# USB.net
KiCad netlist of a schematic drawn in Altium Designer
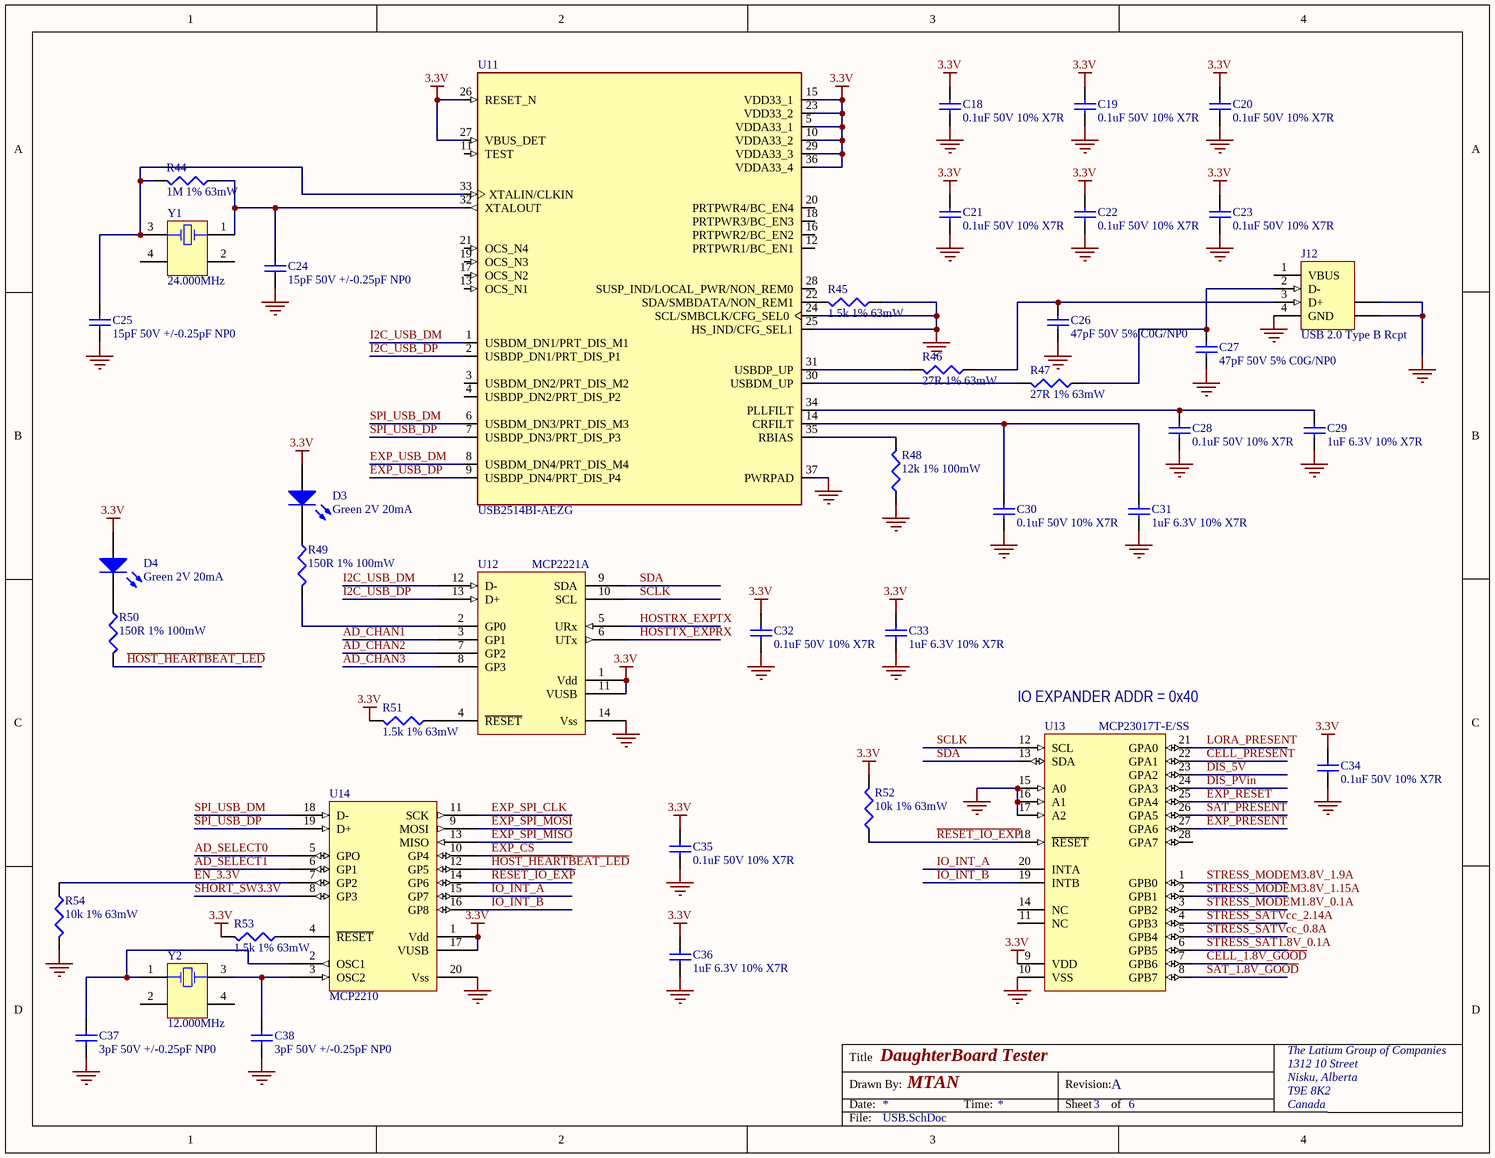
[diagram p0: USB.SchDoc]

(export (version "E")
  (design (tool "Eeschema 10.0.6"))
  (components
    (comp (ref "C18")
      (value "0.1uF 50V 10% X7R")
      (footprint "CAPC1005L")
      (description "Capacitor")
      (libsource (lib "Miscellaneous Devices") (part "Cap"))
    )
    (comp (ref "C19")
      (value "0.1uF 50V 10% X7R")
      (footprint "CAPC1005L")
      (description "Capacitor")
      (libsource (lib "Miscellaneous Devices") (part "Cap"))
    )
    (comp (ref "C20")
      (value "0.1uF 50V 10% X7R")
      (footprint "CAPC1005L")
      (description "Capacitor")
      (libsource (lib "Miscellaneous Devices") (part "Cap"))
    )
    (comp (ref "C21")
      (value "0.1uF 50V 10% X7R")
      (footprint "CAPC1005L")
      (description "Capacitor")
      (libsource (lib "Miscellaneous Devices") (part "Cap"))
    )
    (comp (ref "C22")
      (value "0.1uF 50V 10% X7R")
      (footprint "CAPC1005L")
      (description "Capacitor")
      (libsource (lib "Miscellaneous Devices") (part "Cap"))
    )
    (comp (ref "C23")
      (value "0.1uF 50V 10% X7R")
      (footprint "CAPC1005L")
      (description "Capacitor")
      (libsource (lib "Miscellaneous Devices") (part "Cap"))
    )
    (comp (ref "C24")
      (value "15pF 50V +/-0.25pF NP0")
      (footprint "CAPC1005L")
      (description "Capacitor")
      (libsource (lib "Miscellaneous Devices") (part "Cap"))
    )
    (comp (ref "C25")
      (value "15pF 50V +/-0.25pF NP0")
      (footprint "CAPC1005L")
      (description "Capacitor")
      (libsource (lib "Miscellaneous Devices") (part "Cap"))
    )
    (comp (ref "C26")
      (value "47pF 50V 5% C0G/NP0")
      (footprint "CAPC1005L")
      (description "Capacitor")
      (libsource (lib "Miscellaneous Devices") (part "Cap"))
    )
    (comp (ref "C27")
      (value "47pF 50V 5% C0G/NP0")
      (footprint "CAPC1005L")
      (description "Capacitor")
      (libsource (lib "Miscellaneous Devices") (part "Cap"))
    )
    (comp (ref "C28")
      (value "0.1uF 50V 10% X7R")
      (footprint "CAPC1005L")
      (description "Capacitor")
      (libsource (lib "Miscellaneous Devices") (part "Cap"))
    )
    (comp (ref "C29")
      (value "1uF 6.3V 10% X7R")
      (footprint "CAPC1005L")
      (description "Capacitor")
      (libsource (lib "Miscellaneous Devices") (part "Cap"))
    )
    (comp (ref "C30")
      (value "0.1uF 50V 10% X7R")
      (footprint "CAPC1005L")
      (description "Capacitor")
      (libsource (lib "Miscellaneous Devices") (part "Cap"))
    )
    (comp (ref "C31")
      (value "1uF 6.3V 10% X7R")
      (footprint "CAPC1005L")
      (description "Capacitor")
      (libsource (lib "Miscellaneous Devices") (part "Cap"))
    )
    (comp (ref "C32")
      (value "0.1uF 50V 10% X7R")
      (footprint "CAPC1005L")
      (description "Capacitor")
      (libsource (lib "Miscellaneous Devices") (part "Cap"))
    )
    (comp (ref "C33")
      (value "1uF 6.3V 10% X7R")
      (footprint "CAPC1005L")
      (description "Capacitor")
      (libsource (lib "Miscellaneous Devices") (part "Cap"))
    )
    (comp (ref "C34")
      (value "0.1uF 50V 10% X7R")
      (footprint "CAPC1005L")
      (description "Capacitor")
      (libsource (lib "Miscellaneous Devices") (part "Cap"))
    )
    (comp (ref "C35")
      (value "0.1uF 50V 10% X7R")
      (footprint "CAPC1005L")
      (description "Capacitor")
      (libsource (lib "Miscellaneous Devices") (part "Cap"))
    )
    (comp (ref "C36")
      (value "1uF 6.3V 10% X7R")
      (footprint "CAPC1005L")
      (description "Capacitor")
      (libsource (lib "Miscellaneous Devices") (part "Cap"))
    )
    (comp (ref "C37")
      (value "3pF 50V +/-0.25pF NP0")
      (footprint "CAPC1005L")
      (description "Capacitor")
      (libsource (lib "Miscellaneous Devices") (part "Cap"))
    )
    (comp (ref "C38")
      (value "3pF 50V +/-0.25pF NP0")
      (footprint "CAPC1005L")
      (description "Capacitor")
      (libsource (lib "Miscellaneous Devices") (part "Cap"))
    )
    (comp (ref "D3")
      (value "Green 2V 20mA")
      (footprint "CD1608-0603")
      (description "LED GREEN CLEAR 0603 SMD")
      (fields
        (field (name "MANUFACTURER") "Wurth Electronics Inc")
        (field (name "MANUFACTURER PART NUMBER") "150060VS75000")
      )
      (libsource (lib "Miscellaneous Devices") (part "LED2"))
    )
    (comp (ref "D4")
      (value "Green 2V 20mA")
      (footprint "CD1608-0603")
      (description "LED GREEN CLEAR 0603 SMD")
      (fields
        (field (name "MANUFACTURER") "Wurth Electronics Inc")
        (field (name "MANUFACTURER PART NUMBER") "150060VS75000")
      )
      (libsource (lib "Miscellaneous Devices") (part "LED2"))
    )
    (comp (ref "J12")
      (value "USB 2.0 Type B Rcpt")
      (footprint "1-1734346-1")
      (description "CONN RCPT USB2.0 TYPEB 4P SMD RA")
      (fields
        (field (name "MANUFACTURER") "TE Connectivity AMP Connectors")
        (field (name "MANUFACTURER PART NUMBER") "1-1734346-1")
      )
      (libsource (lib "AMP Serial Bus USB") (part "1-1470156-1"))
    )
    (comp (ref "R44")
      (value "1M 1% 63mW")
      (footprint "RESC1005L")
      (description "Resistor")
      (libsource (lib "Miscellaneous Devices") (part "Res3"))
    )
    (comp (ref "R45")
      (value "1.5k 1% 63mW")
      (footprint "RESC1005L")
      (description "Resistor")
      (libsource (lib "Miscellaneous Devices") (part "Res3"))
    )
    (comp (ref "R46")
      (value "27R 1% 63mW")
      (footprint "RESC1005L")
      (description "Resistor")
      (libsource (lib "Miscellaneous Devices") (part "Res3"))
    )
    (comp (ref "R47")
      (value "27R 1% 63mW")
      (footprint "RESC1005L")
      (description "Resistor")
      (libsource (lib "Miscellaneous Devices") (part "Res3"))
    )
    (comp (ref "R48")
      (value "12k 1% 100mW")
      (footprint "J1-0603")
      (description "Resistor")
      (libsource (lib "Miscellaneous Devices") (part "Res3"))
    )
    (comp (ref "R49")
      (value "150R 1% 100mW")
      (footprint "RESC1608L")
      (description "Resistor")
      (libsource (lib "Miscellaneous Devices") (part "Res3"))
    )
    (comp (ref "R50")
      (value "150R 1% 100mW")
      (footprint "RESC1608L")
      (description "Resistor")
      (libsource (lib "Miscellaneous Devices") (part "Res3"))
    )
    (comp (ref "R51")
      (value "1.5k 1% 63mW")
      (footprint "RESC1005L")
      (description "Resistor")
      (libsource (lib "Miscellaneous Devices") (part "Res3"))
    )
    (comp (ref "R52")
      (value "10k 1% 63mW")
      (footprint "RESC1005L")
      (description "Resistor")
      (libsource (lib "Miscellaneous Devices") (part "Res3"))
    )
    (comp (ref "R53")
      (value "1.5k 1% 63mW")
      (footprint "RESC1005L")
      (description "Resistor")
      (libsource (lib "Miscellaneous Devices") (part "Res3"))
    )
    (comp (ref "R54")
      (value "10k 1% 63mW")
      (footprint "RESC1005L")
      (description "Resistor")
      (libsource (lib "Miscellaneous Devices") (part "Res3"))
    )
    (comp (ref "U11")
      (value "USB2514BI-AEZG")
      (footprint "QFN50P600X600X100-37N")
      (description "IC CONTROLLER USB 36QFN")
      (fields
        (field (name "MANUFACTURER") "Microchip Technology")
        (field (name "MANUFACTURER PART NUMBER") "USB2514BI-AEZG-TR")
      )
      (libsource (lib "USB2514BI-AEZG") (part "USB2514BI-AEZG"))
    )
    (comp (ref "U12")
      (value "MCP2221A")
      (footprint "TSSOP14_L")
      (description "IC USB TO I2C/UART 14TSSOP")
      (fields
        (field (name "MANUFACTURER") "Microchip Technology")
        (field (name "MANUFACTURER PART NUMBER") "MCP2221AT-I/ST")
      )
      (libsource (lib "Latium Component Library") (part "MCP2221A"))
    )
    (comp (ref "U13")
      (value "MCP23017T-E/SS")
      (footprint "SSOP-SS28_L")
      (description "IC I/O EXPANDER 16BIT I2C 28SSOP")
      (fields (field (name "MANUFACTURER") "Microchip Technology"))
      (libsource (lib "Microchip Interface") (part "MCP23017-E/SS"))
    )
    (comp (ref "U14")
      (value "MCP2210")
      (footprint "SSOP20_L")
      (description "IC CONVERTER USB-SPI 20-SSOP")
      (fields
        (field (name "MANUFACTURER") "Microchip Technology")
        (field (name "MANUFACTURER PART NUMBER") "MCP2210T-I/SS")
      )
      (libsource (lib "Latium Component Library") (part "MCP2210"))
    )
    (comp (ref "Y1")
      (value "24.000MHz")
      (footprint "CFPX-5")
      (description "CRYSTAL 24.0000MHZ 18PF SMD")
      (fields
        (field (name "MANUFACTURER PART NUMBER") "TSX-3225 24.0000MF18X-C0")
        (field (name "MANUFACTURER") "Epson")
      )
      (libsource (lib "C-MAC Crystal Oscillator") (part "CFPX-5"))
    )
    (comp (ref "Y2")
      (value "12.000MHz")
      (footprint "CFPX-5")
      (description "CRYSTAL 12.0000MHZ 8PF SMD")
      (fields
        (field (name "MANUFACTURER PART NUMBER") "NX3225SA-12.000M-STD-CRS-2")
        (field (name "MANUFACTURER") "NDK America Inc")
      )
      (libsource (lib "") (part "CFPX-5_1"))
    )
  )
  (nets
    (net (code "1") (name "/AD_CHAN1") (class "Default")
      (node (ref "U12") (pin "3") (pinfunction "GP1_3") (pintype "passive"))
    )
    (net (code "2") (name "/AD_CHAN2") (class "Default")
      (node (ref "U12") (pin "7") (pinfunction "GP2_7") (pintype "passive"))
    )
    (net (code "3") (name "/AD_CHAN3") (class "Default")
      (node (ref "U12") (pin "8") (pinfunction "GP3_8") (pintype "passive"))
    )
    (net (code "4") (name "/AD_SELECT0") (class "Default")
      (node (ref "U14") (pin "5") (pinfunction "GPO_5") (pintype "bidirectional"))
    )
    (net (code "5") (name "/AD_SELECT1") (class "Default")
      (node (ref "U14") (pin "6") (pinfunction "GP1_6") (pintype "bidirectional"))
    )
    (net (code "6") (name "/CELL_PRESENT") (class "Default")
      (node (ref "U13") (pin "22") (pinfunction "GPA1_22") (pintype "bidirectional"))
    )
    (net (code "7") (name "/DIS_5V") (class "Default")
      (node (ref "U13") (pin "23") (pinfunction "GPA2_23") (pintype "bidirectional"))
    )
    (net (code "8") (name "/DIS_PVin") (class "Default")
      (node (ref "U13") (pin "24") (pinfunction "GPA3_24") (pintype "bidirectional"))
    )
    (net (code "9") (name "/EN_3.3V") (class "Default")
      (node (ref "R54") (pin "1") (pinfunction "1_1") (pintype "passive"))
      (node (ref "U14") (pin "7") (pinfunction "GP2_7") (pintype "bidirectional"))
    )
    (net (code "10") (name "/EXP_PRESENT") (class "Default")
      (node (ref "U13") (pin "27") (pinfunction "GPA6_27") (pintype "bidirectional"))
    )
    (net (code "11") (name "/EXP_RESET") (class "Default")
      (node (ref "U13") (pin "25") (pinfunction "GPA4_25") (pintype "bidirectional"))
    )
    (net (code "12") (name "/EXP_SPI_CLK") (class "Default")
      (node (ref "U14") (pin "11") (pinfunction "SCK_11") (pintype "output"))
    )
    (net (code "13") (name "/EXP_SPI_MISO") (class "Default")
      (node (ref "U14") (pin "13") (pinfunction "MISO_13") (pintype "input"))
    )
    (net (code "14") (name "/EXP_SPI_MOSI") (class "Default")
      (node (ref "U14") (pin "9") (pinfunction "MOSI_9") (pintype "output"))
    )
    (net (code "15") (name "/EXP_USB_DM") (class "Default")
      (node (ref "U11") (pin "8") (pinfunction "USBDM_DN4/PRT_DIS_M4_8") (pintype "bidirectional"))
    )
    (net (code "16") (name "/EXP_USB_DP") (class "Default")
      (node (ref "U11") (pin "9") (pinfunction "USBDP_DN4/PRT_DIS_P4_9") (pintype "bidirectional"))
    )
    (net (code "17") (name "/HOSTRX_EXPTX") (class "Default")
      (node (ref "U12") (pin "5") (pinfunction "URx_5") (pintype "input"))
    )
    (net (code "18") (name "/HOSTTX_EXPRX") (class "Default")
      (node (ref "U12") (pin "6") (pinfunction "UTx_6") (pintype "output"))
    )
    (net (code "19") (name "/I2C_USB_DM") (class "Default")
      (node (ref "U11") (pin "1") (pinfunction "USBDM_DN1/PRT_DIS_M1_1") (pintype "bidirectional"))
      (node (ref "U12") (pin "12") (pinfunction "D-_12") (pintype "input"))
    )
    (net (code "20") (name "/I2C_USB_DP") (class "Default")
      (node (ref "U11") (pin "2") (pinfunction "USBDP_DN1/PRT_DIS_P1_2") (pintype "bidirectional"))
      (node (ref "U12") (pin "13") (pinfunction "D+_13") (pintype "input"))
    )
    (net (code "21") (name "/IO_INT_A") (class "Default")
      (node (ref "U13") (pin "20") (pinfunction "INTA_20") (pintype "open_collector"))
      (node (ref "U14") (pin "15") (pinfunction "GP7_15") (pintype "bidirectional"))
    )
    (net (code "22") (name "/IO_INT_B") (class "Default")
      (node (ref "U13") (pin "19") (pinfunction "INTB_19") (pintype "open_collector"))
      (node (ref "U14") (pin "16") (pinfunction "GP8_16") (pintype "bidirectional"))
    )
    (net (code "23") (name "/LORA_PRESENT") (class "Default")
      (node (ref "U13") (pin "21") (pinfunction "GPA0_21") (pintype "bidirectional"))
    )
    (net (code "24") (name "/SAT_PRESENT") (class "Default")
      (node (ref "U13") (pin "26") (pinfunction "GPA5_26") (pintype "bidirectional"))
    )
    (net (code "25") (name "/SCLK") (class "Default")
      (node (ref "U12") (pin "10") (pinfunction "SCL_10") (pintype "open_collector"))
      (node (ref "U13") (pin "12") (pinfunction "SCL_12") (pintype "input"))
    )
    (net (code "26") (name "/SDA") (class "Default")
      (node (ref "U12") (pin "9") (pinfunction "SDA_9") (pintype "open_collector"))
      (node (ref "U13") (pin "13") (pinfunction "SDA_13") (pintype "bidirectional"))
    )
    (net (code "27") (name "/SPI_USB_DM") (class "Default")
      (node (ref "U11") (pin "6") (pinfunction "USBDM_DN3/PRT_DIS_M3_6") (pintype "bidirectional"))
      (node (ref "U14") (pin "18") (pinfunction "D-_18") (pintype "input"))
    )
    (net (code "28") (name "/SPI_USB_DP") (class "Default")
      (node (ref "U11") (pin "7") (pinfunction "USBDP_DN3/PRT_DIS_P3_7") (pintype "bidirectional"))
      (node (ref "U14") (pin "19") (pinfunction "D+_19") (pintype "input"))
    )
    (net (code "29") (name "/STRESS_MODEM1.8V_0.1A") (class "Default")
      (node (ref "U13") (pin "3") (pinfunction "GPB2_3") (pintype "bidirectional"))
    )
    (net (code "30") (name "/STRESS_MODEM3.8V_1.9A") (class "Default")
      (node (ref "U13") (pin "1") (pinfunction "GPB0_1") (pintype "bidirectional"))
    )
    (net (code "31") (name "/STRESS_MODEM3.8V_1.15A") (class "Default")
      (node (ref "U13") (pin "2") (pinfunction "GPB1_2") (pintype "bidirectional"))
    )
    (net (code "32") (name "/STRESS_SAT1.8V_0.1A") (class "Default")
      (node (ref "U13") (pin "6") (pinfunction "GPB5_6") (pintype "bidirectional"))
    )
    (net (code "33") (name "/STRESS_SATVcc_0.8A") (class "Default")
      (node (ref "U13") (pin "5") (pinfunction "GPB4_5") (pintype "bidirectional"))
    )
    (net (code "34") (name "/STRESS_SATVcc_2.14A") (class "Default")
      (node (ref "U13") (pin "4") (pinfunction "GPB3_4") (pintype "bidirectional"))
    )
    (net (code "35") (name "/~{CELL_1.8V_GOOD}") (class "Default")
      (node (ref "U13") (pin "7") (pinfunction "GPB6_7") (pintype "bidirectional"))
    )
    (net (code "36") (name "/~{EXP_CS}") (class "Default")
      (node (ref "U14") (pin "10") (pinfunction "GP4_10") (pintype "bidirectional"))
    )
    (net (code "37") (name "/~{HOST_HEARTBEAT_LED}") (class "Default")
      (node (ref "R50") (pin "2") (pinfunction "2_2") (pintype "passive"))
      (node (ref "U14") (pin "12") (pinfunction "GP5_12") (pintype "bidirectional"))
    )
    (net (code "38") (name "/~{RESET_IO_EXP}") (class "Default")
      (node (ref "R52") (pin "1") (pinfunction "1_1") (pintype "passive"))
      (node (ref "U13") (pin "18") (pinfunction "~{RESET}_18") (pintype "input"))
      (node (ref "U14") (pin "14") (pinfunction "GP6_14") (pintype "bidirectional"))
    )
    (net (code "39") (name "/~{SAT_1.8V_GOOD}") (class "Default")
      (node (ref "U13") (pin "8") (pinfunction "GPB7_8") (pintype "bidirectional"))
    )
    (net (code "40") (name "/~{SHORT_SW3.3V}") (class "Default")
      (node (ref "U14") (pin "8") (pinfunction "GP3_8") (pintype "bidirectional"))
    )
    (net (code "41") (name "3.3V") (class "Default")
      (node (ref "C18") (pin "1") (pinfunction "1_1") (pintype "passive"))
      (node (ref "C19") (pin "1") (pinfunction "1_1") (pintype "passive"))
      (node (ref "C20") (pin "1") (pinfunction "1_1") (pintype "passive"))
      (node (ref "C21") (pin "1") (pinfunction "1_1") (pintype "passive"))
      (node (ref "C22") (pin "1") (pinfunction "1_1") (pintype "passive"))
      (node (ref "C23") (pin "1") (pinfunction "1_1") (pintype "passive"))
      (node (ref "C32") (pin "1") (pinfunction "1_1") (pintype "passive"))
      (node (ref "C33") (pin "1") (pinfunction "1_1") (pintype "passive"))
      (node (ref "C34") (pin "1") (pinfunction "1_1") (pintype "passive"))
      (node (ref "C35") (pin "1") (pinfunction "1_1") (pintype "passive"))
      (node (ref "C36") (pin "1") (pinfunction "1_1") (pintype "passive"))
      (node (ref "D3") (pin "1") (pinfunction "A_1") (pintype "passive"))
      (node (ref "D4") (pin "1") (pinfunction "A_1") (pintype "passive"))
      (node (ref "R51") (pin "2") (pinfunction "2_2") (pintype "passive"))
      (node (ref "R52") (pin "2") (pinfunction "2_2") (pintype "passive"))
      (node (ref "R53") (pin "2") (pinfunction "2_2") (pintype "passive"))
      (node (ref "U11") (pin "10") (pinfunction "VDDA33_2_10") (pintype "power_in"))
      (node (ref "U11") (pin "15") (pinfunction "VDD33_1_15") (pintype "power_in"))
      (node (ref "U11") (pin "23") (pinfunction "VDD33_2_23") (pintype "power_in"))
      (node (ref "U11") (pin "26") (pinfunction "RESET_N_26") (pintype "input"))
      (node (ref "U11") (pin "27") (pinfunction "VBUS_DET_27") (pintype "input"))
      (node (ref "U11") (pin "29") (pinfunction "VDDA33_3_29") (pintype "power_in"))
      (node (ref "U11") (pin "36") (pinfunction "VDDA33_4_36") (pintype "power_in"))
      (node (ref "U11") (pin "5") (pinfunction "VDDA33_1_5") (pintype "power_in"))
      (node (ref "U12") (pin "1") (pinfunction "Vdd_1") (pintype "power_in"))
      (node (ref "U12") (pin "11") (pinfunction "VUSB_11") (pintype "passive"))
      (node (ref "U13") (pin "9") (pinfunction "VDD_9") (pintype "power_in"))
      (node (ref "U14") (pin "1") (pinfunction "Vdd_1") (pintype "power_in"))
      (node (ref "U14") (pin "17") (pinfunction "VUSB_17") (pintype "power_in"))
    )
    (net (code "42") (name "GND") (class "Default")
      (node (ref "C18") (pin "2") (pinfunction "2_2") (pintype "passive"))
      (node (ref "C19") (pin "2") (pinfunction "2_2") (pintype "passive"))
      (node (ref "C20") (pin "2") (pinfunction "2_2") (pintype "passive"))
      (node (ref "C21") (pin "2") (pinfunction "2_2") (pintype "passive"))
      (node (ref "C22") (pin "2") (pinfunction "2_2") (pintype "passive"))
      (node (ref "C23") (pin "2") (pinfunction "2_2") (pintype "passive"))
      (node (ref "C24") (pin "2") (pinfunction "2_2") (pintype "passive"))
      (node (ref "C25") (pin "2") (pinfunction "2_2") (pintype "passive"))
      (node (ref "C26") (pin "2") (pinfunction "2_2") (pintype "passive"))
      (node (ref "C27") (pin "2") (pinfunction "2_2") (pintype "passive"))
      (node (ref "C28") (pin "2") (pinfunction "2_2") (pintype "passive"))
      (node (ref "C29") (pin "2") (pinfunction "2_2") (pintype "passive"))
      (node (ref "C30") (pin "2") (pinfunction "2_2") (pintype "passive"))
      (node (ref "C31") (pin "2") (pinfunction "2_2") (pintype "passive"))
      (node (ref "C32") (pin "2") (pinfunction "2_2") (pintype "passive"))
      (node (ref "C33") (pin "2") (pinfunction "2_2") (pintype "passive"))
      (node (ref "C34") (pin "2") (pinfunction "2_2") (pintype "passive"))
      (node (ref "C35") (pin "2") (pinfunction "2_2") (pintype "passive"))
      (node (ref "C36") (pin "2") (pinfunction "2_2") (pintype "passive"))
      (node (ref "C37") (pin "2") (pinfunction "2_2") (pintype "passive"))
      (node (ref "C38") (pin "2") (pinfunction "2_2") (pintype "passive"))
      (node (ref "J12") (pin "4") (pinfunction "GND_4") (pintype "power_in"))
      (node (ref "J12") (pin "MP1") (pinfunction "SHLD_MP1") (pintype "passive"))
      (node (ref "J12") (pin "MP2") (pinfunction "SHLD_MP2") (pintype "passive"))
      (node (ref "R45") (pin "1") (pinfunction "1_1") (pintype "passive"))
      (node (ref "R48") (pin "1") (pinfunction "1_1") (pintype "passive"))
      (node (ref "R54") (pin "2") (pinfunction "2_2") (pintype "passive"))
      (node (ref "U11") (pin "24") (pinfunction "SCL/SMBCLK/CFG_SEL0_24") (pintype "bidirectional"))
      (node (ref "U11") (pin "25") (pinfunction "HS_IND/CFG_SEL1_25") (pintype "bidirectional"))
      (node (ref "U11") (pin "37") (pinfunction "PWRPAD_37") (pintype "power_in"))
      (node (ref "U12") (pin "14") (pinfunction "Vss_14") (pintype "power_in"))
      (node (ref "U13") (pin "10") (pinfunction "VSS_10") (pintype "power_in"))
      (node (ref "U13") (pin "15") (pinfunction "A0_15") (pintype "input"))
      (node (ref "U13") (pin "16") (pinfunction "A1_16") (pintype "input"))
      (node (ref "U13") (pin "17") (pinfunction "A2_17") (pintype "input"))
      (node (ref "U14") (pin "20") (pinfunction "Vss_20") (pintype "power_in"))
    )
    (net (code "43") (name "Net-(D3-K)") (class "Default")
      (node (ref "D3") (pin "2") (pinfunction "K_2") (pintype "passive"))
      (node (ref "R49") (pin "1") (pinfunction "1_1") (pintype "passive"))
    )
    (net (code "44") (name "Net-(D4-K)") (class "Default")
      (node (ref "D4") (pin "2") (pinfunction "K_2") (pintype "passive"))
      (node (ref "R50") (pin "1") (pinfunction "1_1") (pintype "passive"))
    )
    (net (code "45") (name "Net-(J12-D+)") (class "Default")
      (node (ref "C26") (pin "1") (pinfunction "1_1") (pintype "passive"))
      (node (ref "J12") (pin "3") (pinfunction "D+_3") (pintype "input"))
      (node (ref "R46") (pin "1") (pinfunction "1_1") (pintype "passive"))
    )
    (net (code "46") (name "Net-(J12-D-)") (class "Default")
      (node (ref "C27") (pin "1") (pinfunction "1_1") (pintype "passive"))
      (node (ref "J12") (pin "2") (pinfunction "D-_2") (pintype "input"))
      (node (ref "R47") (pin "1") (pinfunction "1_1") (pintype "passive"))
    )
    (net (code "47") (name "Net-(U11-CRFILT)") (class "Default")
      (node (ref "C30") (pin "1") (pinfunction "1_1") (pintype "passive"))
      (node (ref "C31") (pin "1") (pinfunction "1_1") (pintype "passive"))
      (node (ref "U11") (pin "14") (pinfunction "CRFILT_14") (pintype "passive"))
    )
    (net (code "48") (name "Net-(U11-PLLFILT)") (class "Default")
      (node (ref "C28") (pin "1") (pinfunction "1_1") (pintype "passive"))
      (node (ref "C29") (pin "1") (pinfunction "1_1") (pintype "passive"))
      (node (ref "U11") (pin "34") (pinfunction "PLLFILT_34") (pintype "passive"))
    )
    (net (code "49") (name "Net-(U11-RBIAS)") (class "Default")
      (node (ref "R48") (pin "2") (pinfunction "2_2") (pintype "passive"))
      (node (ref "U11") (pin "35") (pinfunction "RBIAS_35") (pintype "passive"))
    )
    (net (code "50") (name "Net-(U11-SDA{slash}SMBDATA{slash}NON_REM1)") (class "Default")
      (node (ref "R45") (pin "2") (pinfunction "2_2") (pintype "passive"))
      (node (ref "U11") (pin "22") (pinfunction "SDA/SMBDATA/NON_REM1_22") (pintype "bidirectional"))
    )
    (net (code "51") (name "Net-(U11-USBDM_UP)") (class "Default")
      (node (ref "R47") (pin "2") (pinfunction "2_2") (pintype "passive"))
      (node (ref "U11") (pin "30") (pinfunction "USBDM_UP_30") (pintype "bidirectional"))
    )
    (net (code "52") (name "Net-(U11-USBDP_UP)") (class "Default")
      (node (ref "R46") (pin "2") (pinfunction "2_2") (pintype "passive"))
      (node (ref "U11") (pin "31") (pinfunction "USBDP_UP_31") (pintype "bidirectional"))
    )
    (net (code "53") (name "Net-(U11-XTALIN{slash}CLKIN)") (class "Default")
      (node (ref "C25") (pin "1") (pinfunction "1_1") (pintype "passive"))
      (node (ref "R44") (pin "2") (pinfunction "2_2") (pintype "passive"))
      (node (ref "U11") (pin "33") (pinfunction "XTALIN/CLKIN_33") (pintype "input"))
      (node (ref "Y1") (pin "3") (pinfunction "OSC2_3") (pintype "passive"))
    )
    (net (code "54") (name "Net-(U11-XTALOUT)") (class "Default")
      (node (ref "C24") (pin "1") (pinfunction "1_1") (pintype "passive"))
      (node (ref "R44") (pin "1") (pinfunction "1_1") (pintype "passive"))
      (node (ref "U11") (pin "32") (pinfunction "XTALOUT_32") (pintype "output"))
      (node (ref "Y1") (pin "1") (pinfunction "OSC1_1") (pintype "passive"))
    )
    (net (code "55") (name "Net-(U12-GP0)") (class "Default")
      (node (ref "R49") (pin "2") (pinfunction "2_2") (pintype "passive"))
      (node (ref "U12") (pin "2") (pinfunction "GP0_2") (pintype "passive"))
    )
    (net (code "56") (name "Net-(U12-~{RESET})") (class "Default")
      (node (ref "R51") (pin "1") (pinfunction "1_1") (pintype "passive"))
      (node (ref "U12") (pin "4") (pinfunction "~{RESET}_4") (pintype "passive"))
    )
    (net (code "57") (name "Net-(U14-OSC1)") (class "Default")
      (node (ref "C37") (pin "1") (pinfunction "1_1") (pintype "passive"))
      (node (ref "U14") (pin "2") (pinfunction "OSC1_2") (pintype "output"))
      (node (ref "Y2") (pin "1") (pinfunction "OSC1_1") (pintype "passive"))
    )
    (net (code "58") (name "Net-(U14-OSC2)") (class "Default")
      (node (ref "C38") (pin "1") (pinfunction "1_1") (pintype "passive"))
      (node (ref "U14") (pin "3") (pinfunction "OSC2_3") (pintype "input"))
      (node (ref "Y2") (pin "3") (pinfunction "OSC2_3") (pintype "passive"))
    )
    (net (code "59") (name "Net-(U14-~{RESET})") (class "Default")
      (node (ref "R53") (pin "1") (pinfunction "1_1") (pintype "passive"))
      (node (ref "U14") (pin "4") (pinfunction "~{RESET}_4") (pintype "open_collector"))
    )
    (net (code "60") (name "unconnected-(J12-VBUS-Pad1)") (class "Default")
      (node (ref "J12") (pin "1") (pinfunction "VBUS_1") (pintype "power_in"))
    )
    (net (code "61") (name "unconnected-(U11-OCS_N1-Pad13)") (class "Default")
      (node (ref "U11") (pin "13") (pinfunction "OCS_N1_13") (pintype "input"))
    )
    (net (code "62") (name "unconnected-(U11-OCS_N2-Pad17)") (class "Default")
      (node (ref "U11") (pin "17") (pinfunction "OCS_N2_17") (pintype "input"))
    )
    (net (code "63") (name "unconnected-(U11-OCS_N3-Pad19)") (class "Default")
      (node (ref "U11") (pin "19") (pinfunction "OCS_N3_19") (pintype "input"))
    )
    (net (code "64") (name "unconnected-(U11-OCS_N4-Pad21)") (class "Default")
      (node (ref "U11") (pin "21") (pinfunction "OCS_N4_21") (pintype "input"))
    )
    (net (code "65") (name "unconnected-(U11-PRTPWR1{slash}BC_EN1-Pad12)") (class "Default")
      (node (ref "U11") (pin "12") (pinfunction "PRTPWR1/BC_EN1_12") (pintype "bidirectional"))
    )
    (net (code "66") (name "unconnected-(U11-PRTPWR2{slash}BC_EN2-Pad16)") (class "Default")
      (node (ref "U11") (pin "16") (pinfunction "PRTPWR2/BC_EN2_16") (pintype "bidirectional"))
    )
    (net (code "67") (name "unconnected-(U11-PRTPWR3{slash}BC_EN3-Pad18)") (class "Default")
      (node (ref "U11") (pin "18") (pinfunction "PRTPWR3/BC_EN3_18") (pintype "bidirectional"))
    )
    (net (code "68") (name "unconnected-(U11-PRTPWR4{slash}BC_EN4-Pad20)") (class "Default")
      (node (ref "U11") (pin "20") (pinfunction "PRTPWR4/BC_EN4_20") (pintype "bidirectional"))
    )
    (net (code "69") (name "unconnected-(U11-SUSP_IND{slash}LOCAL_PWR{slash}NON_REM0-Pad28)") (class "Default")
      (node (ref "U11") (pin "28") (pinfunction "SUSP_IND/LOCAL_PWR/NON_REM0_28") (pintype "bidirectional"))
    )
    (net (code "70") (name "unconnected-(U11-TEST-Pad11)") (class "Default")
      (node (ref "U11") (pin "11") (pinfunction "TEST_11") (pintype "input"))
    )
    (net (code "71") (name "unconnected-(U11-USBDM_DN2{slash}PRT_DIS_M2-Pad3)") (class "Default")
      (node (ref "U11") (pin "3") (pinfunction "USBDM_DN2/PRT_DIS_M2_3") (pintype "bidirectional"))
    )
    (net (code "72") (name "unconnected-(U11-USBDP_DN2{slash}PRT_DIS_P2-Pad4)") (class "Default")
      (node (ref "U11") (pin "4") (pinfunction "USBDP_DN2/PRT_DIS_P2_4") (pintype "bidirectional"))
    )
    (net (code "73") (name "unconnected-(U13-GPA7-Pad28)") (class "Default")
      (node (ref "U13") (pin "28") (pinfunction "GPA7_28") (pintype "bidirectional"))
    )
    (net (code "74") (name "unconnected-(U13-NC-Pad11)") (class "Default")
      (node (ref "U13") (pin "11") (pinfunction "NC_11") (pintype "passive"))
    )
    (net (code "75") (name "unconnected-(U13-NC-Pad14)") (class "Default")
      (node (ref "U13") (pin "14") (pinfunction "NC_14") (pintype "passive"))
    )
    (net (code "76") (name "unconnected-(Y1-NC-Pad2)") (class "Default")
      (node (ref "Y1") (pin "2") (pinfunction "NC_2") (pintype "passive"))
    )
    (net (code "77") (name "unconnected-(Y1-NC-Pad4)") (class "Default")
      (node (ref "Y1") (pin "4") (pinfunction "NC_4") (pintype "passive"))
    )
    (net (code "78") (name "unconnected-(Y2-NC-Pad2)") (class "Default")
      (node (ref "Y2") (pin "2") (pinfunction "NC_2") (pintype "passive"))
    )
    (net (code "79") (name "unconnected-(Y2-NC-Pad4)") (class "Default")
      (node (ref "Y2") (pin "4") (pinfunction "NC_4") (pintype "passive"))
    )
  )
)
